# Power.net
KiCad netlist of a schematic drawn in Altium Designer
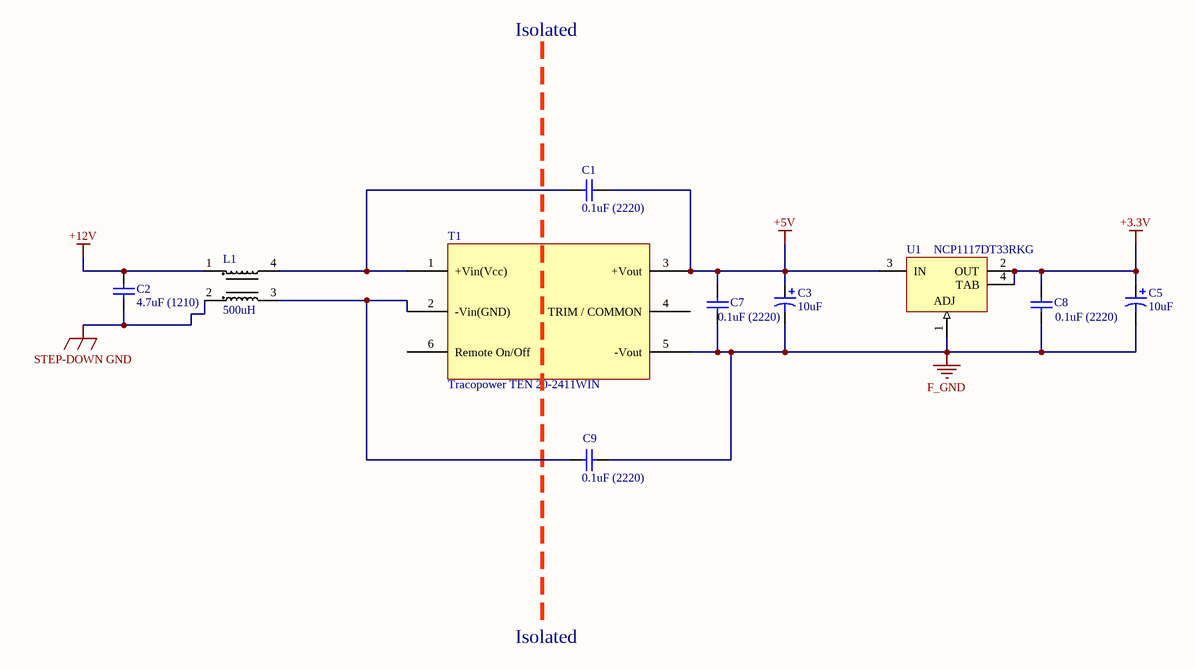
[diagram p0: Power.SchDoc]

(export (version "E")
  (design (tool "Eeschema 10.0.6"))
  (components
    (comp (ref "C1")
      (value "0.1uF (2220)")
      (footprint "PCB-vinf2si7ml1r5i2zfsci-1")
      (description "2220 1 uF 250 V ±10% Tolerance X7R SMT Multilayer Ceramic Capacitor")
      (fields (field (name "MANUFACTURER PART NUMBER") "GRM55DR72E105KW01L"))
      (libsource (lib "CommunityVault") (part "SYM-869a4f93a212595d-1"))
    )
    (comp (ref "C2")
      (value "4.7uF (1210)")
      (footprint "PCB-2fbb0vau3p468w0y920g-1")
      (description "1210 4.7 uF 50 V ±10% Tolerance X7R SMT Multilayer Ceramic Capacitor")
      (fields (field (name "MANUFACTURER PART NUMBER") "GRM32ER71H475KA88L"))
      (libsource (lib "FavoritesLibrary") (part "SYM-8d884480570e524f-1"))
    )
    (comp (ref "C3")
      (value "10uF")
      (footprint "PCB-ibkib54e90xysjsqnert-1")
      (description "Capacitor Alum Elec, 10uf, 100v, 20%, Capacitor Alum Elec, 10uf, 100v, 20%, Smd, Full Reel")
      (fields (field (name "MANUFACTURER PART NUMBER") "EEE-2AA100UP"))
      (libsource (lib "CommunityVault") (part "SYM-da8810cd3d6e054f-1"))
    )
    (comp (ref "C5")
      (value "10uF")
      (footprint "PCB-ibkib54e90xysjsqnert-1")
      (description "Capacitor Alum Elec, 10uf, 100v, 20%, Capacitor Alum Elec, 10uf, 100v, 20%, Smd, Full Reel")
      (fields (field (name "MANUFACTURER PART NUMBER") "EEE-2AA100UP"))
      (libsource (lib "CommunityVault") (part "SYM-da8810cd3d6e054f-1"))
    )
    (comp (ref "C7")
      (value "0.1uF (2220)")
      (footprint "PCB-vinf2si7ml1r5i2zfsci-1")
      (description "2220 1 uF 250 V ±10% Tolerance X7R SMT Multilayer Ceramic Capacitor")
      (fields (field (name "MANUFACTURER PART NUMBER") "GRM55DR72E105KW01L"))
      (libsource (lib "CommunityVault") (part "SYM-869a4f93a212595d-1"))
    )
    (comp (ref "C8")
      (value "0.1uF (2220)")
      (footprint "PCB-vinf2si7ml1r5i2zfsci-1")
      (description "2220 1 uF 250 V ±10% Tolerance X7R SMT Multilayer Ceramic Capacitor")
      (fields (field (name "MANUFACTURER PART NUMBER") "GRM55DR72E105KW01L"))
      (libsource (lib "CommunityVault") (part "SYM-869a4f93a212595d-1"))
    )
    (comp (ref "C9")
      (value "0.1uF (2220)")
      (footprint "PCB-vinf2si7ml1r5i2zfsci-1")
      (description "2220 1 uF 250 V ±10% Tolerance X7R SMT Multilayer Ceramic Capacitor")
      (fields (field (name "MANUFACTURER PART NUMBER") "GRM55DR72E105KW01L"))
      (libsource (lib "CommunityVault") (part "SYM-869a4f93a212595d-1"))
    )
    (comp (ref "L1")
      (value "500uH")
      (footprint "PCB-kl08ucybfpyhun58dexm-1")
      (description "Common Mode Chokes Dual 1mH 10kHz 15A 3.3mOhm DCR Thru-Hole T/R")
      (fields (field (name "MANUFACTURER PART NUMBER") "7448031501"))
      (libsource (lib "CommunityVault") (part "CMP-c51a0edc807c1add-4"))
    )
    (comp (ref "T1")
      (value "Tracopower TEN 20-2411WIN")
      (footprint "PCBComponent_1")
      (description "20 W Watt, 9-36VDCVin, Quad Output, 5V@4A General Purpose DC-DC Converter in standard 1 x 2")
      (fields (field (name "MANUFACTURER PART NUMBER") "TEN 20-2411WIN"))
      (libsource (lib "CommunityVault") (part "CMP-cff406adefdb1033-7"))
    )
    (comp (ref "U1")
      (value "NCP1117DT33RKG")
      (footprint "PCB-1493942-1")
      (description "IC REG LDO 3.3V 1A DPAK")
      (libsource (lib "CommunityVault") (part "SYM-1493942-1"))
    )
  )
  (nets
    (net (code "1") (name "+3.3V") (class "Default")
      (node (ref "C5") (pin "1") (pinfunction "1_1") (pintype "passive"))
      (node (ref "C8") (pin "1") (pinfunction "1_1") (pintype "passive"))
      (node (ref "U1") (pin "2") (pinfunction "OUT_2") (pintype "power_in"))
      (node (ref "U1") (pin "4") (pinfunction "TAB_4") (pintype "power_in"))
    )
    (net (code "2") (name "+5V") (class "Default")
      (node (ref "C1") (pin "1") (pinfunction "1_1") (pintype "passive"))
      (node (ref "C3") (pin "1") (pinfunction "1_1") (pintype "passive"))
      (node (ref "C7") (pin "1") (pinfunction "1_1") (pintype "passive"))
      (node (ref "T1") (pin "3") (pinfunction "+Vout_3") (pintype "passive"))
      (node (ref "U1") (pin "3") (pinfunction "IN_3") (pintype "power_in"))
    )
    (net (code "3") (name "+12V") (class "Default")
      (node (ref "C2") (pin "2") (pinfunction "2_2") (pintype "passive"))
      (node (ref "L1") (pin "1") (pinfunction "1_1") (pintype "passive"))
    )
    (net (code "4") (name "F_GND") (class "Default")
      (node (ref "C3") (pin "2") (pinfunction "2_2") (pintype "passive"))
      (node (ref "C5") (pin "2") (pinfunction "2_2") (pintype "passive"))
      (node (ref "C7") (pin "2") (pinfunction "2_2") (pintype "passive"))
      (node (ref "C8") (pin "2") (pinfunction "2_2") (pintype "passive"))
      (node (ref "C9") (pin "1") (pinfunction "1_1") (pintype "passive"))
      (node (ref "T1") (pin "5") (pinfunction "-Vout_5") (pintype "passive"))
      (node (ref "U1") (pin "1") (pinfunction "ADJ_1") (pintype "input"))
    )
    (net (code "5") (name "Net-(T1-+Vin(Vcc))") (class "Default")
      (node (ref "C1") (pin "2") (pinfunction "2_2") (pintype "passive"))
      (node (ref "L1") (pin "4") (pinfunction "4_4") (pintype "passive"))
      (node (ref "T1") (pin "1") (pinfunction "+Vin(Vcc)_1") (pintype "passive"))
    )
    (net (code "6") (name "Net-(T1--Vin(GND))") (class "Default")
      (node (ref "C9") (pin "2") (pinfunction "2_2") (pintype "passive"))
      (node (ref "L1") (pin "3") (pinfunction "3_3") (pintype "passive"))
      (node (ref "T1") (pin "2") (pinfunction "-Vin(GND)_2") (pintype "passive"))
    )
    (net (code "7") (name "STEP-DOWN GND") (class "Default")
      (node (ref "C2") (pin "1") (pinfunction "1_1") (pintype "passive"))
      (node (ref "L1") (pin "2") (pinfunction "2_2") (pintype "passive"))
    )
    (net (code "8") (name "unconnected-(T1-Remote_On{slash}Off-Pad6)") (class "Default")
      (node (ref "T1") (pin "6") (pinfunction "Remote_On/Off_6") (pintype "passive"))
    )
    (net (code "9") (name "unconnected-(T1-TRIM_{slash}_COMMON-Pad4)") (class "Default")
      (node (ref "T1") (pin "4") (pinfunction "TRIM_/_COMMON_4") (pintype "passive"))
    )
  )
)
